# Sensor.net
KiCad netlist of a schematic drawn in Altium Designer
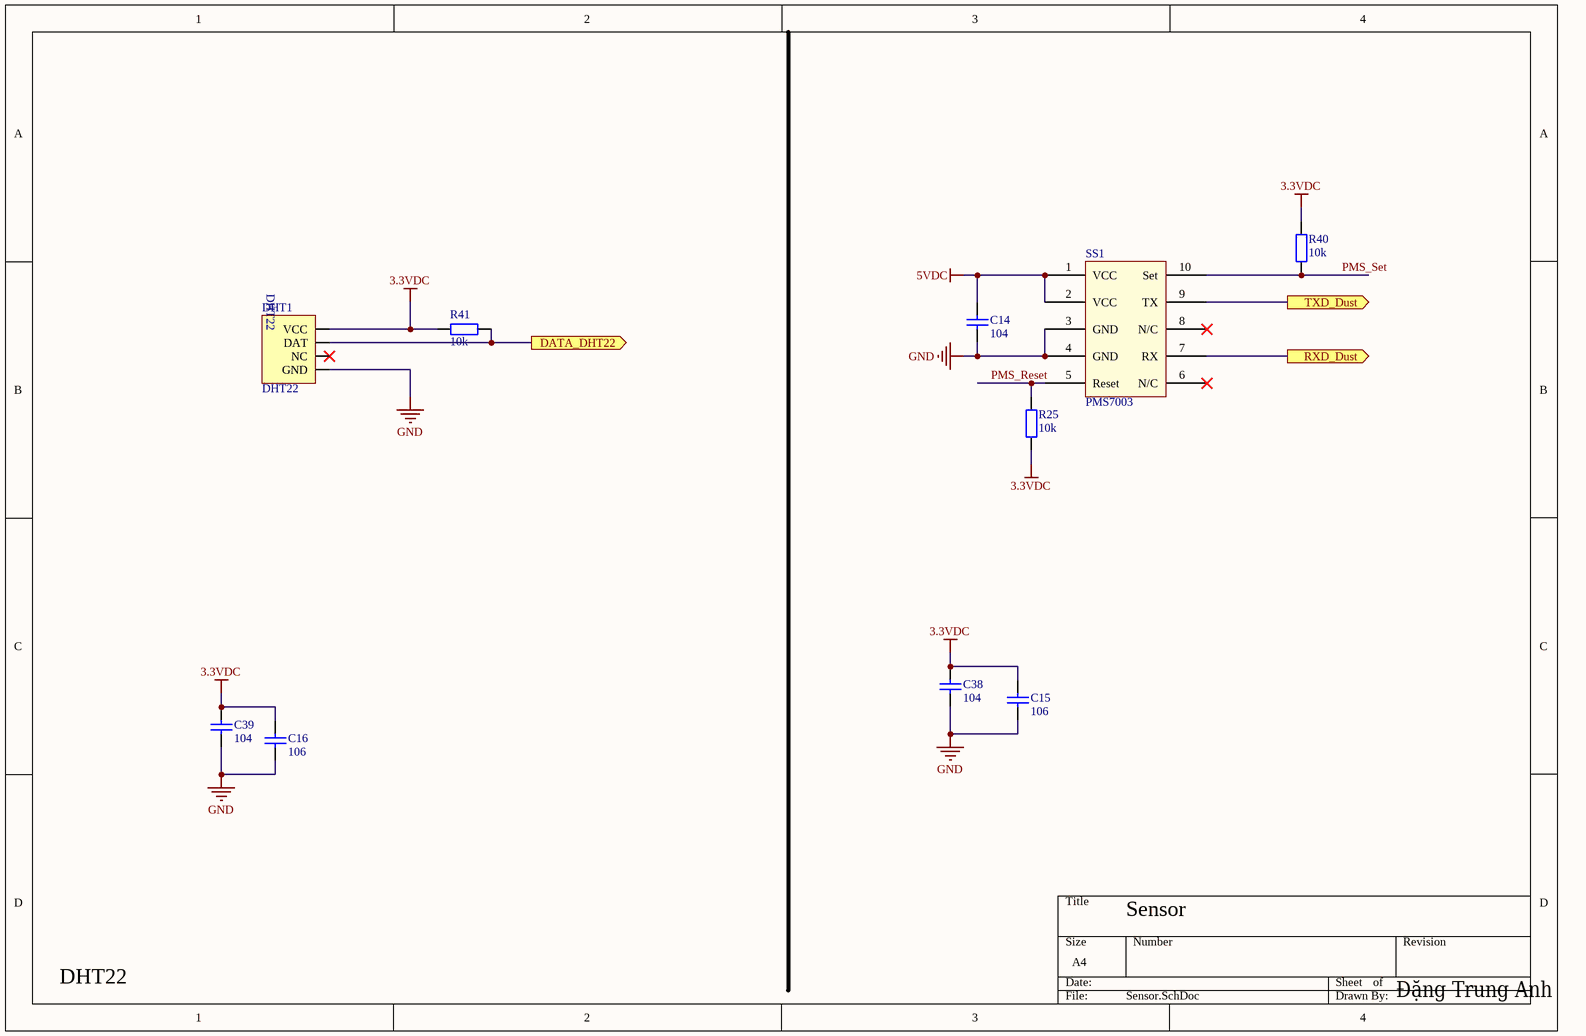
[diagram p0: Sensor.SchDoc]

(export (version "E")
  (design (tool "Eeschema 10.0.6"))
  (components
    (comp (ref "C14")
      (value "104")
      (footprint "tu 0805")
      (description "Dán")
      (libsource (lib "THU VIEN SCH") (part "Tu 0805 104 50V 10%"))
    )
    (comp (ref "C15")
      (value "106")
      (footprint "Tu 0805")
      (description "Dán")
      (libsource (lib "THU VIEN SCH") (part "Tu 0805 106 16V 10%"))
    )
    (comp (ref "C16")
      (value "106")
      (footprint "Tu 0805")
      (description "Dán")
      (libsource (lib "THU VIEN SCH") (part "Tu 0805 106 16V 10%"))
    )
    (comp (ref "C38")
      (value "104")
      (footprint "Tu 0805")
      (description "Dán")
      (libsource (lib "THU VIEN SCH") (part "Tu 104"))
    )
    (comp (ref "C39")
      (value "104")
      (footprint "Tu 0805")
      (description "Dán")
      (libsource (lib "THU VIEN SCH") (part "Tu 104"))
    )
    (comp (ref "DHT1")
      (value "DHT22")
      (footprint "DHT22")
      (fields
        (field (name "MANUFACTURER") "Würth Elektronik eiSos GmbH")
        (field (name "PARTNO") "613004143121")
        (field (name "CREATED BY") "Karrer Zheng")
      )
      (libsource (lib "TechMT.VN_Lib_Project v2") (part "DHT22"))
    )
    (comp (ref "R25")
      (value "10k")
      (footprint "tro smd 0805")
      (description "Dán")
      (libsource (lib "THU VIEN SCH") (part "Tro 0805 5% 10k"))
    )
    (comp (ref "R40")
      (value "10k")
      (footprint "tro smd 0805")
      (description "Dán")
      (libsource (lib "THU VIEN SCH") (part "Tro 0805 5% 10k"))
    )
    (comp (ref "R41")
      (value "10k")
      (footprint "tro smd 0805")
      (description "Dán")
      (libsource (lib "THU VIEN SCH") (part "Tro 0805 5% 10k"))
    )
    (comp (ref "SS1")
      (value "PMS7003")
      (footprint "PMS7003")
      (libsource (lib "Integrated_Library") (part "PMS7003"))
    )
  )
  (nets
    (net (code "1") (name "/DATA_DHT22") (class "Default")
      (node (ref "DHT1") (pin "2") (pinfunction "DAT_2") (pintype "passive"))
      (node (ref "R41") (pin "2") (pinfunction "2_2") (pintype "passive"))
    )
    (net (code "2") (name "/PMS_Reset") (class "Default")
      (node (ref "R25") (pin "2") (pinfunction "2_2") (pintype "passive"))
      (node (ref "SS1") (pin "5") (pinfunction "Reset_5") (pintype "passive"))
    )
    (net (code "3") (name "/PMS_Set") (class "Default")
      (node (ref "R40") (pin "2") (pinfunction "2_2") (pintype "passive"))
      (node (ref "SS1") (pin "10") (pinfunction "Set_10") (pintype "passive"))
    )
    (net (code "4") (name "/RXD_Dust") (class "Default")
      (node (ref "SS1") (pin "7") (pinfunction "RX_7") (pintype "passive"))
    )
    (net (code "5") (name "/TXD_Dust") (class "Default")
      (node (ref "SS1") (pin "9") (pinfunction "TX_9") (pintype "passive"))
    )
    (net (code "6") (name "3.3VDC") (class "Default")
      (node (ref "C15") (pin "2") (pinfunction "2_2") (pintype "passive"))
      (node (ref "C16") (pin "2") (pinfunction "2_2") (pintype "passive"))
      (node (ref "C38") (pin "2") (pinfunction "2_2") (pintype "passive"))
      (node (ref "C39") (pin "2") (pinfunction "2_2") (pintype "passive"))
      (node (ref "DHT1") (pin "1") (pinfunction "VCC_1") (pintype "passive"))
      (node (ref "R25") (pin "1") (pinfunction "1_1") (pintype "passive"))
      (node (ref "R40") (pin "1") (pinfunction "1_1") (pintype "passive"))
      (node (ref "R41") (pin "1") (pinfunction "1_1") (pintype "passive"))
    )
    (net (code "7") (name "5VDC") (class "Default")
      (node (ref "C14") (pin "1") (pinfunction "1_1") (pintype "passive"))
      (node (ref "SS1") (pin "1") (pinfunction "VCC_1") (pintype "passive"))
      (node (ref "SS1") (pin "2") (pinfunction "VCC_2") (pintype "passive"))
    )
    (net (code "8") (name "GND") (class "Default")
      (node (ref "C14") (pin "2") (pinfunction "2_2") (pintype "passive"))
      (node (ref "C15") (pin "1") (pinfunction "1_1") (pintype "passive"))
      (node (ref "C16") (pin "1") (pinfunction "1_1") (pintype "passive"))
      (node (ref "C38") (pin "1") (pinfunction "1_1") (pintype "passive"))
      (node (ref "C39") (pin "1") (pinfunction "1_1") (pintype "passive"))
      (node (ref "DHT1") (pin "4") (pinfunction "GND_4") (pintype "passive"))
      (node (ref "SS1") (pin "3") (pinfunction "GND_3") (pintype "passive"))
      (node (ref "SS1") (pin "4") (pinfunction "GND_4") (pintype "passive"))
    )
    (net (code "9") (name "unconnected-(DHT1-NC-Pad3)") (class "Default")
      (node (ref "DHT1") (pin "3") (pinfunction "NC_3") (pintype "passive+no_connect"))
    )
    (net (code "10") (name "unconnected-(SS1-N{slash}C-Pad6)") (class "Default")
      (node (ref "SS1") (pin "6") (pinfunction "N/C_6") (pintype "passive+no_connect"))
    )
    (net (code "11") (name "unconnected-(SS1-N{slash}C-Pad8)") (class "Default")
      (node (ref "SS1") (pin "8") (pinfunction "N/C_8") (pintype "passive+no_connect"))
    )
  )
)
